# Schematic_v26.net
KiCad netlist of a schematic drawn in EAGLE
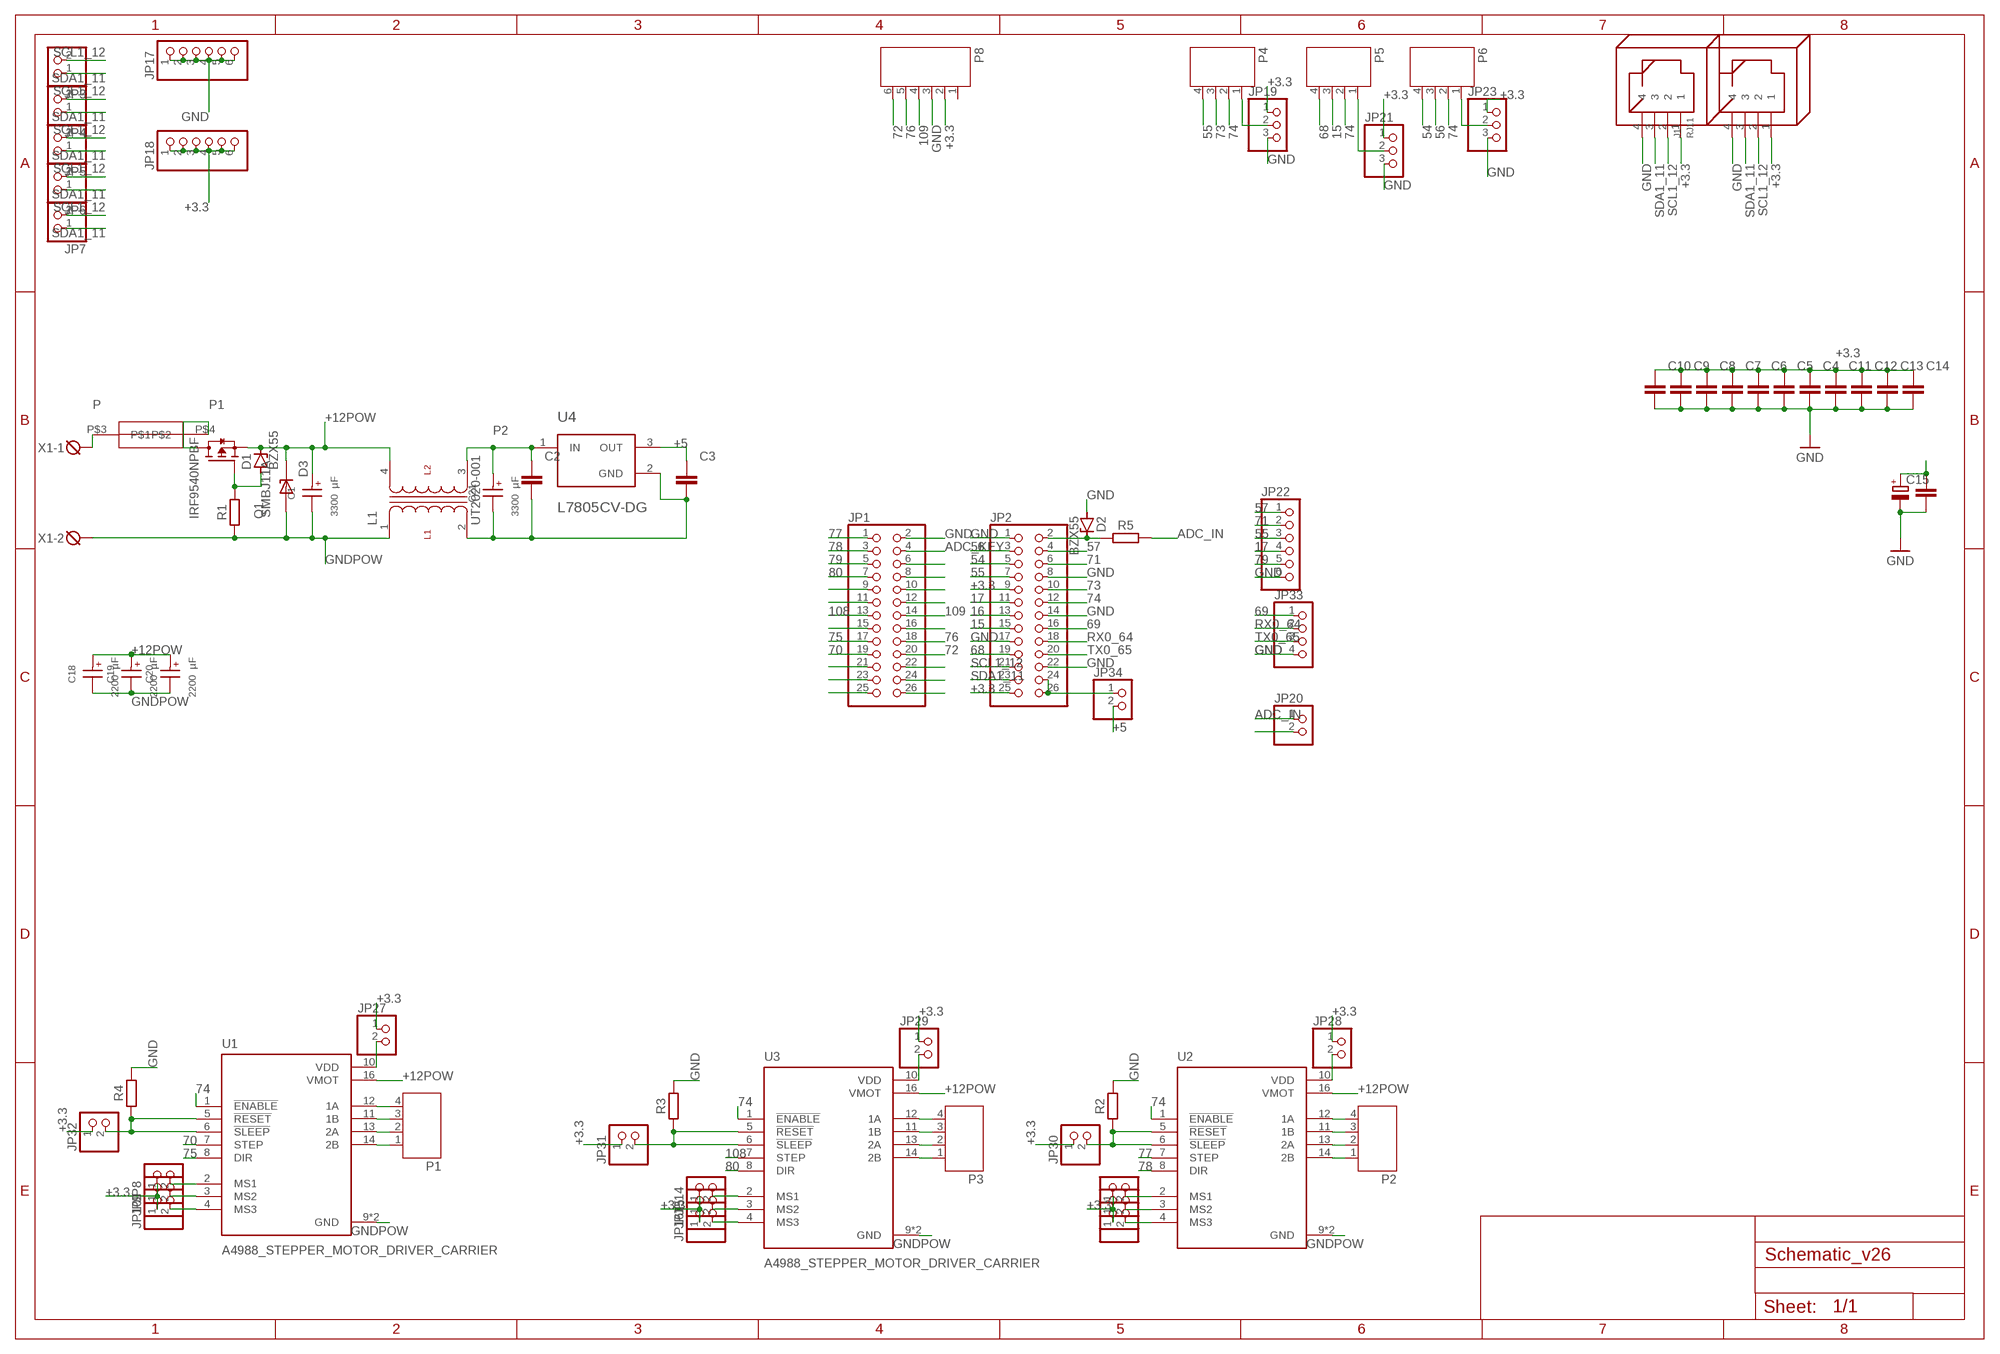
[diagram p0: schematic, sheet 1]

(export (version "E")
  (design (tool "Eeschema 10.0.6"))
  (components
    (comp (ref "C1")
      (value "3300 µF")
      (footprint "eagle-import:WCAP-AT1H_13X20(DXL)")
      (libsource (lib "eagle-import") (part "WCAP-AT1H_13X20_860240278009"))
    )
    (comp (ref "C2")
      (value "C_CHIP-1206(3216-METRIC)")
      (footprint "eagle-import:CAPC3216X135")
      (libsource (lib "eagle-import") (part "CCHIP-1206(3216-METRIC)_"))
    )
    (comp (ref "C3")
      (value "C_CHIP-0603(1608-METRIC)")
      (footprint "eagle-import:CAPC1608X85")
      (libsource (lib "eagle-import") (part "CCHIP-0603(1608-METRIC)_"))
    )
    (comp (ref "C4")
      (value "C_CHIP-0603(1608-METRIC)")
      (footprint "eagle-import:CAPC1608X85")
      (libsource (lib "eagle-import") (part "CCHIP-0603(1608-METRIC)_"))
    )
    (comp (ref "C5")
      (value "C_CHIP-0603(1608-METRIC)")
      (footprint "eagle-import:CAPC1608X85")
      (libsource (lib "eagle-import") (part "CCHIP-0603(1608-METRIC)_"))
    )
    (comp (ref "C6")
      (value "C_CHIP-0603(1608-METRIC)")
      (footprint "eagle-import:CAPC1608X85")
      (libsource (lib "eagle-import") (part "CCHIP-0603(1608-METRIC)_"))
    )
    (comp (ref "C7")
      (value "C_CHIP-0603(1608-METRIC)")
      (footprint "eagle-import:CAPC1608X85")
      (libsource (lib "eagle-import") (part "CCHIP-0603(1608-METRIC)_"))
    )
    (comp (ref "C8")
      (value "C_CHIP-0603(1608-METRIC)")
      (footprint "eagle-import:CAPC1608X85")
      (libsource (lib "eagle-import") (part "CCHIP-0603(1608-METRIC)_"))
    )
    (comp (ref "C9")
      (value "C_CHIP-0603(1608-METRIC)")
      (footprint "eagle-import:CAPC1608X85")
      (libsource (lib "eagle-import") (part "CCHIP-0603(1608-METRIC)_"))
    )
    (comp (ref "C10")
      (value "C_CHIP-0603(1608-METRIC)")
      (footprint "eagle-import:CAPC1608X85")
      (libsource (lib "eagle-import") (part "CCHIP-0603(1608-METRIC)_"))
    )
    (comp (ref "C11")
      (value "C_CHIP-1206(3216-METRIC)")
      (footprint "eagle-import:CAPC3216X135")
      (libsource (lib "eagle-import") (part "CCHIP-1206(3216-METRIC)_"))
    )
    (comp (ref "C12")
      (value "C_CHIP-1206(3216-METRIC)")
      (footprint "eagle-import:CAPC3216X135")
      (libsource (lib "eagle-import") (part "CCHIP-1206(3216-METRIC)_"))
    )
    (comp (ref "C13")
      (value "C_CHIP-1206(3216-METRIC)")
      (footprint "eagle-import:CAPC3216X135")
      (libsource (lib "eagle-import") (part "CCHIP-1206(3216-METRIC)_"))
    )
    (comp (ref "C14")
      (value "C_CHIP-1206(3216-METRIC)")
      (footprint "eagle-import:CAPC3216X135")
      (libsource (lib "eagle-import") (part "CCHIP-1206(3216-METRIC)_"))
    )
    (comp (ref "C15")
      (value "C-POL_RADIAL-11MM-DIA")
      (footprint "eagle-import:CAPPRD508W65D1000H1100B")
      (libsource (lib "eagle-import") (part "C-POLRADIAL-11MM-DIA_"))
    )
    (comp (ref "C18")
      (value "2200 µF")
      (footprint "eagle-import:WCAP-AT1H_13X20(DXL)")
      (libsource (lib "eagle-import") (part "WCAP-AT1H_13X20_860240278009"))
    )
    (comp (ref "C19")
      (value "2200 µF")
      (footprint "eagle-import:WCAP-AT1H_13X20(DXL)")
      (libsource (lib "eagle-import") (part "WCAP-AT1H_13X20_860240278009"))
    )
    (comp (ref "C20")
      (value "2200 µF")
      (footprint "eagle-import:WCAP-AT1H_13X20(DXL)")
      (libsource (lib "eagle-import") (part "WCAP-AT1H_13X20_860240278009"))
    )
    (comp (ref "C21")
      (value "3300 µF")
      (footprint "eagle-import:WCAP-AT1H_13X20(DXL)")
      (libsource (lib "eagle-import") (part "WCAP-AT1H_13X20_860240278009"))
    )
    (comp (ref "C22")
      (value "C_CHIP-1206(3216-METRIC)")
      (footprint "eagle-import:CAPC3216X135")
      (libsource (lib "eagle-import") (part "CCHIP-1206(3216-METRIC)_"))
    )
    (comp (ref "D1")
      (value "BZX55")
      (footprint "eagle-import:DO35Z10")
      (libsource (lib "eagle-import") (part "BZX55"))
    )
    (comp (ref "D2")
      (value "BZX55")
      (footprint "eagle-import:DO35Z10")
      (libsource (lib "eagle-import") (part "BZX55"))
    )
    (comp (ref "D3")
      (value "SMBJ11A")
      (footprint "eagle-import:DIOM4336X265N")
      (fields (field (name "MF") "Taiwan Semiconductor"))
      (libsource (lib "eagle-import") (part "SMBJ11A"))
    )
    (comp (ref "J1")
      (value "RJ11")
      (footprint "eagle-import:RJ11")
      (libsource (lib "eagle-import") (part "RJ11"))
    )
    (comp (ref "J3")
      (value "RJ11")
      (footprint "eagle-import:RJ11")
      (libsource (lib "eagle-import") (part "RJ11"))
    )
    (comp (ref "JP1")
      (value "PINHD-2X13")
      (footprint "eagle-import:2X13")
      (libsource (lib "eagle-import") (part "PINHD-2X13"))
    )
    (comp (ref "JP2")
      (value "PINHD-2X13")
      (footprint "eagle-import:2X13")
      (libsource (lib "eagle-import") (part "PINHD-2X13"))
    )
    (comp (ref "JP3")
      (value "PINHD-1X2")
      (footprint "eagle-import:1X02")
      (libsource (lib "eagle-import") (part "PINHD-1X2"))
    )
    (comp (ref "JP4")
      (value "PINHD-1X2")
      (footprint "eagle-import:1X02")
      (libsource (lib "eagle-import") (part "PINHD-1X2"))
    )
    (comp (ref "JP5")
      (value "PINHD-1X2")
      (footprint "eagle-import:1X02")
      (libsource (lib "eagle-import") (part "PINHD-1X2"))
    )
    (comp (ref "JP6")
      (value "PINHD-1X2")
      (footprint "eagle-import:1X02")
      (libsource (lib "eagle-import") (part "PINHD-1X2"))
    )
    (comp (ref "JP7")
      (value "PINHD-1X2")
      (footprint "eagle-import:1X02")
      (libsource (lib "eagle-import") (part "PINHD-1X2"))
    )
    (comp (ref "JP8")
      (value "PINHD-1X2")
      (footprint "eagle-import:1X02")
      (libsource (lib "eagle-import") (part "PINHD-1X2"))
    )
    (comp (ref "JP9")
      (value "PINHD-1X2")
      (footprint "eagle-import:1X02")
      (libsource (lib "eagle-import") (part "PINHD-1X2"))
    )
    (comp (ref "JP10")
      (value "PINHD-1X2")
      (footprint "eagle-import:1X02")
      (libsource (lib "eagle-import") (part "PINHD-1X2"))
    )
    (comp (ref "JP11")
      (value "PINHD-1X2")
      (footprint "eagle-import:1X02")
      (libsource (lib "eagle-import") (part "PINHD-1X2"))
    )
    (comp (ref "JP12")
      (value "PINHD-1X2")
      (footprint "eagle-import:1X02")
      (libsource (lib "eagle-import") (part "PINHD-1X2"))
    )
    (comp (ref "JP13")
      (value "PINHD-1X2")
      (footprint "eagle-import:1X02")
      (libsource (lib "eagle-import") (part "PINHD-1X2"))
    )
    (comp (ref "JP14")
      (value "PINHD-1X2")
      (footprint "eagle-import:1X02")
      (libsource (lib "eagle-import") (part "PINHD-1X2"))
    )
    (comp (ref "JP15")
      (value "PINHD-1X2")
      (footprint "eagle-import:1X02")
      (libsource (lib "eagle-import") (part "PINHD-1X2"))
    )
    (comp (ref "JP16")
      (value "PINHD-1X2")
      (footprint "eagle-import:1X02")
      (libsource (lib "eagle-import") (part "PINHD-1X2"))
    )
    (comp (ref "JP17")
      (value "PINHD-1X6")
      (footprint "eagle-import:1X06")
      (libsource (lib "eagle-import") (part "PINHD-1X6"))
    )
    (comp (ref "JP18")
      (value "PINHD-1X6")
      (footprint "eagle-import:1X06")
      (libsource (lib "eagle-import") (part "PINHD-1X6"))
    )
    (comp (ref "JP19")
      (value "PINHD-1X3")
      (footprint "eagle-import:1X03")
      (libsource (lib "eagle-import") (part "PINHD-1X3"))
    )
    (comp (ref "JP20")
      (value "PINHD-1X2")
      (footprint "eagle-import:1X02")
      (libsource (lib "eagle-import") (part "PINHD-1X2"))
    )
    (comp (ref "JP21")
      (value "PINHD-1X3")
      (footprint "eagle-import:1X03")
      (libsource (lib "eagle-import") (part "PINHD-1X3"))
    )
    (comp (ref "JP22")
      (value "PINHD-1X6")
      (footprint "eagle-import:1X06")
      (libsource (lib "eagle-import") (part "PINHD-1X6"))
    )
    (comp (ref "JP23")
      (value "PINHD-1X3")
      (footprint "eagle-import:1X03")
      (libsource (lib "eagle-import") (part "PINHD-1X3"))
    )
    (comp (ref "JP27")
      (value "PINHD-1X2")
      (footprint "eagle-import:1X02")
      (libsource (lib "eagle-import") (part "PINHD-1X2"))
    )
    (comp (ref "JP28")
      (value "PINHD-1X2")
      (footprint "eagle-import:1X02")
      (libsource (lib "eagle-import") (part "PINHD-1X2"))
    )
    (comp (ref "JP29")
      (value "PINHD-1X2")
      (footprint "eagle-import:1X02")
      (libsource (lib "eagle-import") (part "PINHD-1X2"))
    )
    (comp (ref "JP30")
      (value "PINHD-1X2")
      (footprint "eagle-import:1X02")
      (libsource (lib "eagle-import") (part "PINHD-1X2"))
    )
    (comp (ref "JP31")
      (value "PINHD-1X2")
      (footprint "eagle-import:1X02")
      (libsource (lib "eagle-import") (part "PINHD-1X2"))
    )
    (comp (ref "JP32")
      (value "PINHD-1X2")
      (footprint "eagle-import:1X02")
      (libsource (lib "eagle-import") (part "PINHD-1X2"))
    )
    (comp (ref "JP33")
      (value "PINHD-1X4")
      (footprint "eagle-import:1X04")
      (libsource (lib "eagle-import") (part "PINHD-1X4"))
    )
    (comp (ref "JP34")
      (value "PINHD-1X2")
      (footprint "eagle-import:1X02")
      (libsource (lib "eagle-import") (part "PINHD-1X2"))
    )
    (comp (ref "L1")
      (value "UT2020-001")
      (footprint "eagle-import:IND_UT2020-001")
      (fields (field (name "MF") "Triad Magnetics"))
      (libsource (lib "eagle-import") (part "UT2020-001"))
    )
    (comp (ref "P1")
      (value "JST-PH4")
      (footprint "eagle-import:JST-PH4")
      (libsource (lib "eagle-import") (part "JST-PH4"))
    )
    (comp (ref "P2")
      (value "JST-PH4")
      (footprint "eagle-import:JST-PH4")
      (libsource (lib "eagle-import") (part "JST-PH4"))
    )
    (comp (ref "P3")
      (value "JST-PH4")
      (footprint "eagle-import:JST-PH4")
      (libsource (lib "eagle-import") (part "JST-PH4"))
    )
    (comp (ref "P4")
      (value "JST-PH4")
      (footprint "eagle-import:JST-PH4")
      (libsource (lib "eagle-import") (part "JST-PH4"))
    )
    (comp (ref "P5")
      (value "JST-PH4")
      (footprint "eagle-import:JST-PH4")
      (libsource (lib "eagle-import") (part "JST-PH4"))
    )
    (comp (ref "P6")
      (value "JST-PH4")
      (footprint "eagle-import:JST-PH4")
      (libsource (lib "eagle-import") (part "JST-PH4"))
    )
    (comp (ref "P8")
      (value "JST-PH6")
      (footprint "eagle-import:JST-PH6")
      (libsource (lib "eagle-import") (part "JST-PH6"))
    )
    (comp (ref "Q1")
      (value "IRF9540NPBF")
      (footprint "eagle-import:TO254P1052X465X1989-3")
      (fields (field (name "MF") "Infineon Technologies"))
      (libsource (lib "eagle-import") (part "IRF9540NPBF"))
    )
    (comp (ref "R1")
      (value "R_AXIAL-7.2MM-PITCH")
      (footprint "eagle-import:RESAD724W46L381D178B")
      (libsource (lib "eagle-import") (part "RAXIAL-7.2MM-PITCH_"))
    )
    (comp (ref "R2")
      (value "R_CHIP-1206(3216-METRIC)")
      (footprint "eagle-import:RESC3216X70")
      (libsource (lib "eagle-import") (part "RCHIP-1206(3216-METRIC)_"))
    )
    (comp (ref "R3")
      (value "R_CHIP-1206(3216-METRIC)")
      (footprint "eagle-import:RESC3216X70")
      (libsource (lib "eagle-import") (part "RCHIP-1206(3216-METRIC)_"))
    )
    (comp (ref "R4")
      (value "R_CHIP-1206(3216-METRIC)")
      (footprint "eagle-import:RESC3216X70")
      (libsource (lib "eagle-import") (part "RCHIP-1206(3216-METRIC)_"))
    )
    (comp (ref "R5")
      (value "R_CHIP-1206(3216-METRIC)")
      (footprint "eagle-import:RESC3216X70")
      (libsource (lib "eagle-import") (part "RCHIP-1206(3216-METRIC)_"))
    )
    (comp (ref "U$1")
      (value "POJ")
      (footprint "eagle-import:POJ")
      (libsource (lib "eagle-import") (part "POJ"))
    )
    (comp (ref "U1")
      (value "A4988_STEPPER_MOTOR_DRIVER_CARRIER")
      (footprint "eagle-import:MODULE_A4988_STEPPER_MOTOR_DRIVER_CARRIER")
      (fields (field (name "MF") "Pololu") (field (name "MP") "A4988 STEPPER MOTOR DRIVER CARRIER"))
      (libsource (lib "eagle-import") (part "A4988_STEPPER_MOTOR_DRIVER_CARRIER"))
    )
    (comp (ref "U2")
      (value "A4988_STEPPER_MOTOR_DRIVER_CARRIER")
      (footprint "eagle-import:MODULE_A4988_STEPPER_MOTOR_DRIVER_CARRIER")
      (fields (field (name "MF") "Pololu") (field (name "MP") "A4988 STEPPER MOTOR DRIVER CARRIER"))
      (libsource (lib "eagle-import") (part "A4988_STEPPER_MOTOR_DRIVER_CARRIER"))
    )
    (comp (ref "U3")
      (value "A4988_STEPPER_MOTOR_DRIVER_CARRIER")
      (footprint "eagle-import:MODULE_A4988_STEPPER_MOTOR_DRIVER_CARRIER")
      (fields (field (name "MF") "Pololu") (field (name "MP") "A4988 STEPPER MOTOR DRIVER CARRIER"))
      (libsource (lib "eagle-import") (part "A4988_STEPPER_MOTOR_DRIVER_CARRIER"))
    )
    (comp (ref "U4")
      (value "L7805CV-DG")
      (footprint "eagle-import:TO255P1040X460X2890-3")
      (fields (field (name "MF") "STMicroelectronics"))
      (libsource (lib "eagle-import") (part "L7805CV-DG"))
    )
    (comp (ref "X1")
      (value "DG3XX-02-3.5")
      (footprint "eagle-import:DG350-3.5-02P")
      (libsource (lib "eagle-import") (part "DG3XX-02-3.5"))
    )
  )
  (nets
    (net (code "1") (name "/+3.3") (class "Default")
      (node (ref "C10") (pin "1") (pinfunction "1_1") (pintype "passive"))
      (node (ref "C11") (pin "1") (pinfunction "1_1") (pintype "passive"))
      (node (ref "C12") (pin "1") (pinfunction "1_1") (pintype "passive"))
      (node (ref "C13") (pin "1") (pinfunction "1_1") (pintype "passive"))
      (node (ref "C14") (pin "1") (pinfunction "1_1") (pintype "passive"))
      (node (ref "C4") (pin "1") (pinfunction "1_1") (pintype "passive"))
      (node (ref "C5") (pin "1") (pinfunction "1_1") (pintype "passive"))
      (node (ref "C6") (pin "1") (pinfunction "1_1") (pintype "passive"))
      (node (ref "C7") (pin "1") (pinfunction "1_1") (pintype "passive"))
      (node (ref "C8") (pin "1") (pinfunction "1_1") (pintype "passive"))
      (node (ref "C9") (pin "1") (pinfunction "1_1") (pintype "passive"))
      (node (ref "J1") (pin "1") (pinfunction "1_1") (pintype "bidirectional"))
      (node (ref "J3") (pin "1") (pinfunction "1_1") (pintype "bidirectional"))
      (node (ref "JP10") (pin "1") (pinfunction "1_1") (pintype "passive"))
      (node (ref "JP11") (pin "1") (pinfunction "1_1") (pintype "passive"))
      (node (ref "JP12") (pin "1") (pinfunction "1_1") (pintype "passive"))
      (node (ref "JP13") (pin "1") (pinfunction "1_1") (pintype "passive"))
      (node (ref "JP14") (pin "1") (pinfunction "1_1") (pintype "passive"))
      (node (ref "JP15") (pin "1") (pinfunction "1_1") (pintype "passive"))
      (node (ref "JP16") (pin "1") (pinfunction "1_1") (pintype "passive"))
      (node (ref "JP18") (pin "1") (pinfunction "1_1") (pintype "passive"))
      (node (ref "JP18") (pin "2") (pinfunction "2_2") (pintype "passive"))
      (node (ref "JP18") (pin "3") (pinfunction "3_3") (pintype "passive"))
      (node (ref "JP18") (pin "4") (pinfunction "4_4") (pintype "passive"))
      (node (ref "JP18") (pin "5") (pinfunction "5_5") (pintype "passive"))
      (node (ref "JP18") (pin "6") (pinfunction "6_6") (pintype "passive"))
      (node (ref "JP19") (pin "1") (pinfunction "1_1") (pintype "passive"))
      (node (ref "JP2") (pin "25") (pinfunction "25_25") (pintype "passive"))
      (node (ref "JP2") (pin "9") (pinfunction "9_9") (pintype "passive"))
      (node (ref "JP21") (pin "1") (pinfunction "1_1") (pintype "passive"))
      (node (ref "JP23") (pin "1") (pinfunction "1_1") (pintype "passive"))
      (node (ref "JP27") (pin "1") (pinfunction "1_1") (pintype "passive"))
      (node (ref "JP28") (pin "1") (pinfunction "1_1") (pintype "passive"))
      (node (ref "JP29") (pin "1") (pinfunction "1_1") (pintype "passive"))
      (node (ref "JP30") (pin "1") (pinfunction "1_1") (pintype "passive"))
      (node (ref "JP31") (pin "1") (pinfunction "1_1") (pintype "passive"))
      (node (ref "JP32") (pin "1") (pinfunction "1_1") (pintype "passive"))
      (node (ref "JP8") (pin "1") (pinfunction "1_1") (pintype "passive"))
      (node (ref "JP9") (pin "1") (pinfunction "1_1") (pintype "passive"))
      (node (ref "P8") (pin "2") (pinfunction "2_2") (pintype "passive"))
    )
    (net (code "2") (name "/+5") (class "Default")
      (node (ref "C15") (pin "1") (pinfunction "+_1") (pintype "passive"))
      (node (ref "C22") (pin "1") (pinfunction "1_1") (pintype "passive"))
      (node (ref "C3") (pin "1") (pinfunction "1_1") (pintype "passive"))
      (node (ref "JP34") (pin "2") (pinfunction "2_2") (pintype "passive"))
      (node (ref "U4") (pin "3") (pinfunction "OUT_3") (pintype "output"))
    )
    (net (code "3") (name "/+12POW") (class "Default")
      (node (ref "C1") (pin "1") (pinfunction "+_1") (pintype "passive"))
      (node (ref "C18") (pin "1") (pinfunction "+_1") (pintype "passive"))
      (node (ref "C19") (pin "1") (pinfunction "+_1") (pintype "passive"))
      (node (ref "C20") (pin "1") (pinfunction "+_1") (pintype "passive"))
      (node (ref "D1") (pin "C") (pinfunction "C_C") (pintype "passive"))
      (node (ref "D3") (pin "C") (pinfunction "C_C") (pintype "passive"))
      (node (ref "L1") (pin "4") (pinfunction "4_4") (pintype "passive"))
      (node (ref "Q1") (pin "3") (pinfunction "S_3") (pintype "passive"))
      (node (ref "U1") (pin "16") (pinfunction "VMOT_16") (pintype "power_in"))
      (node (ref "U2") (pin "16") (pinfunction "VMOT_16") (pintype "power_in"))
      (node (ref "U3") (pin "16") (pinfunction "VMOT_16") (pintype "power_in"))
    )
    (net (code "4") (name "/15") (class "Default")
      (node (ref "JP2") (pin "15") (pinfunction "15_15") (pintype "passive"))
      (node (ref "P5") (pin "3") (pinfunction "3_3") (pintype "passive"))
    )
    (net (code "5") (name "/16") (class "Default")
      (node (ref "JP2") (pin "13") (pinfunction "13_13") (pintype "passive"))
    )
    (net (code "6") (name "/17") (class "Default")
      (node (ref "JP2") (pin "11") (pinfunction "11_11") (pintype "passive"))
      (node (ref "JP22") (pin "4") (pinfunction "4_4") (pintype "passive"))
    )
    (net (code "7") (name "/54") (class "Default")
      (node (ref "JP2") (pin "5") (pinfunction "5_5") (pintype "passive"))
      (node (ref "P6") (pin "4") (pinfunction "4_4") (pintype "passive"))
    )
    (net (code "8") (name "/55") (class "Default")
      (node (ref "JP2") (pin "7") (pinfunction "7_7") (pintype "passive"))
      (node (ref "JP22") (pin "3") (pinfunction "3_3") (pintype "passive"))
      (node (ref "P4") (pin "4") (pinfunction "4_4") (pintype "passive"))
    )
    (net (code "9") (name "/56") (class "Default")
      (node (ref "JP2") (pin "3") (pinfunction "3_3") (pintype "passive"))
      (node (ref "P6") (pin "3") (pinfunction "3_3") (pintype "passive"))
    )
    (net (code "10") (name "/57") (class "Default")
      (node (ref "JP2") (pin "4") (pinfunction "4_4") (pintype "passive"))
      (node (ref "JP22") (pin "1") (pinfunction "1_1") (pintype "passive"))
    )
    (net (code "11") (name "/68") (class "Default")
      (node (ref "JP2") (pin "19") (pinfunction "19_19") (pintype "passive"))
      (node (ref "P5") (pin "4") (pinfunction "4_4") (pintype "passive"))
    )
    (net (code "12") (name "/69") (class "Default")
      (node (ref "JP2") (pin "16") (pinfunction "16_16") (pintype "passive"))
      (node (ref "JP33") (pin "1") (pinfunction "1_1") (pintype "passive"))
    )
    (net (code "13") (name "/70") (class "Default")
      (node (ref "JP1") (pin "19") (pinfunction "19_19") (pintype "passive"))
      (node (ref "U1") (pin "7") (pinfunction "STEP_7") (pintype "input"))
    )
    (net (code "14") (name "/71") (class "Default")
      (node (ref "JP2") (pin "6") (pinfunction "6_6") (pintype "passive"))
      (node (ref "JP22") (pin "2") (pinfunction "2_2") (pintype "passive"))
    )
    (net (code "15") (name "/72") (class "Default")
      (node (ref "JP1") (pin "20") (pinfunction "20_20") (pintype "passive"))
      (node (ref "P8") (pin "6") (pinfunction "6_6") (pintype "passive"))
    )
    (net (code "16") (name "/73") (class "Default")
      (node (ref "JP2") (pin "10") (pinfunction "10_10") (pintype "passive"))
      (node (ref "P4") (pin "3") (pinfunction "3_3") (pintype "passive"))
    )
    (net (code "17") (name "/74") (class "Default")
      (node (ref "JP2") (pin "12") (pinfunction "12_12") (pintype "passive"))
      (node (ref "P4") (pin "2") (pinfunction "2_2") (pintype "passive"))
      (node (ref "P5") (pin "2") (pinfunction "2_2") (pintype "passive"))
      (node (ref "P6") (pin "2") (pinfunction "2_2") (pintype "passive"))
      (node (ref "U1") (pin "1") (pinfunction "~{ENABLE}_1") (pintype "input"))
      (node (ref "U2") (pin "1") (pinfunction "~{ENABLE}_1") (pintype "input"))
      (node (ref "U3") (pin "1") (pinfunction "~{ENABLE}_1") (pintype "input"))
    )
    (net (code "18") (name "/75") (class "Default")
      (node (ref "JP1") (pin "17") (pinfunction "17_17") (pintype "passive"))
      (node (ref "U1") (pin "8") (pinfunction "DIR_8") (pintype "input"))
    )
    (net (code "19") (name "/76") (class "Default")
      (node (ref "JP1") (pin "18") (pinfunction "18_18") (pintype "passive"))
      (node (ref "P8") (pin "5") (pinfunction "5_5") (pintype "passive"))
    )
    (net (code "20") (name "/77") (class "Default")
      (node (ref "JP1") (pin "1") (pinfunction "1_1") (pintype "passive"))
      (node (ref "U2") (pin "7") (pinfunction "STEP_7") (pintype "input"))
    )
    (net (code "21") (name "/78") (class "Default")
      (node (ref "JP1") (pin "3") (pinfunction "3_3") (pintype "passive"))
      (node (ref "U2") (pin "8") (pinfunction "DIR_8") (pintype "input"))
    )
    (net (code "22") (name "/79") (class "Default")
      (node (ref "JP1") (pin "5") (pinfunction "5_5") (pintype "passive"))
      (node (ref "JP22") (pin "5") (pinfunction "5_5") (pintype "passive"))
    )
    (net (code "23") (name "/80") (class "Default")
      (node (ref "JP1") (pin "7") (pinfunction "7_7") (pintype "passive"))
      (node (ref "U3") (pin "8") (pinfunction "DIR_8") (pintype "input"))
    )
    (net (code "24") (name "/108") (class "Default")
      (node (ref "JP1") (pin "13") (pinfunction "13_13") (pintype "passive"))
      (node (ref "U3") (pin "7") (pinfunction "STEP_7") (pintype "input"))
    )
    (net (code "25") (name "/109") (class "Default")
      (node (ref "JP1") (pin "14") (pinfunction "14_14") (pintype "passive"))
      (node (ref "P8") (pin "4") (pinfunction "4_4") (pintype "passive"))
    )
    (net (code "26") (name "/ADC_IN") (class "Default")
      (node (ref "JP20") (pin "1") (pinfunction "1_1") (pintype "passive"))
      (node (ref "R5") (pin "2") (pinfunction "2_2") (pintype "passive"))
    )
    (net (code "27") (name "/ADC_KEY") (class "Default")
      (node (ref "JP1") (pin "4") (pinfunction "4_4") (pintype "passive"))
    )
    (net (code "28") (name "/GNDPOW") (class "Default")
      (node (ref "C1") (pin "2") (pinfunction "-_2") (pintype "passive"))
      (node (ref "C18") (pin "2") (pinfunction "-_2") (pintype "passive"))
      (node (ref "C19") (pin "2") (pinfunction "-_2") (pintype "passive"))
      (node (ref "C20") (pin "2") (pinfunction "-_2") (pintype "passive"))
      (node (ref "D3") (pin "A") (pinfunction "A_A") (pintype "passive"))
      (node (ref "L1") (pin "1") (pinfunction "1_1") (pintype "passive"))
      (node (ref "R1") (pin "1") (pinfunction "1_1") (pintype "passive"))
      (node (ref "U1") (pin "15") (pinfunction "GND_15") (pintype "power_in"))
      (node (ref "U1") (pin "9") (pinfunction "GND_9") (pintype "power_in"))
      (node (ref "U2") (pin "15") (pinfunction "GND_15") (pintype "power_in"))
      (node (ref "U2") (pin "9") (pinfunction "GND_9") (pintype "power_in"))
      (node (ref "U3") (pin "15") (pinfunction "GND_15") (pintype "power_in"))
      (node (ref "U3") (pin "9") (pinfunction "GND_9") (pintype "power_in"))
      (node (ref "X1") (pin "2") (pinfunction "KL_2") (pintype "passive"))
    )
    (net (code "29") (name "/P") (class "Default")
      (node (ref "U$1") (pin "P$3") (pinfunction "P$1_P$3") (pintype "bidirectional"))
      (node (ref "X1") (pin "1") (pinfunction "KL_1") (pintype "passive"))
    )
    (net (code "30") (name "/P1") (class "Default")
      (node (ref "Q1") (pin "2") (pinfunction "D_2") (pintype "passive"))
      (node (ref "U$1") (pin "P$4") (pinfunction "P$2_P$4") (pintype "bidirectional"))
    )
    (net (code "31") (name "/P2") (class "Default")
      (node (ref "C2") (pin "1") (pinfunction "1_1") (pintype "passive"))
      (node (ref "C21") (pin "1") (pinfunction "+_1") (pintype "passive"))
      (node (ref "L1") (pin "3") (pinfunction "3_3") (pintype "passive"))
      (node (ref "U4") (pin "1") (pinfunction "IN_1") (pintype "input"))
    )
    (net (code "32") (name "/RX0_64") (class "Default")
      (node (ref "JP2") (pin "18") (pinfunction "18_18") (pintype "passive"))
      (node (ref "JP33") (pin "2") (pinfunction "2_2") (pintype "passive"))
    )
    (net (code "33") (name "/SCL1_12") (class "Default")
      (node (ref "J1") (pin "2") (pinfunction "2_2") (pintype "bidirectional"))
      (node (ref "J3") (pin "2") (pinfunction "2_2") (pintype "bidirectional"))
      (node (ref "JP2") (pin "21") (pinfunction "21_21") (pintype "passive"))
      (node (ref "JP3") (pin "2") (pinfunction "2_2") (pintype "passive"))
      (node (ref "JP4") (pin "2") (pinfunction "2_2") (pintype "passive"))
      (node (ref "JP5") (pin "2") (pinfunction "2_2") (pintype "passive"))
      (node (ref "JP6") (pin "2") (pinfunction "2_2") (pintype "passive"))
      (node (ref "JP7") (pin "2") (pinfunction "2_2") (pintype "passive"))
    )
    (net (code "34") (name "/SDA1_11") (class "Default")
      (node (ref "J1") (pin "3") (pinfunction "3_3") (pintype "bidirectional"))
      (node (ref "J3") (pin "3") (pinfunction "3_3") (pintype "bidirectional"))
      (node (ref "JP2") (pin "23") (pinfunction "23_23") (pintype "passive"))
      (node (ref "JP3") (pin "1") (pinfunction "1_1") (pintype "passive"))
      (node (ref "JP4") (pin "1") (pinfunction "1_1") (pintype "passive"))
      (node (ref "JP5") (pin "1") (pinfunction "1_1") (pintype "passive"))
      (node (ref "JP6") (pin "1") (pinfunction "1_1") (pintype "passive"))
      (node (ref "JP7") (pin "1") (pinfunction "1_1") (pintype "passive"))
    )
    (net (code "35") (name "/TX0_65") (class "Default")
      (node (ref "JP2") (pin "20") (pinfunction "20_20") (pintype "passive"))
      (node (ref "JP33") (pin "3") (pinfunction "3_3") (pintype "passive"))
    )
    (net (code "36") (name "GND") (class "Default")
      (node (ref "C10") (pin "2") (pinfunction "2_2") (pintype "passive"))
      (node (ref "C11") (pin "2") (pinfunction "2_2") (pintype "passive"))
      (node (ref "C12") (pin "2") (pinfunction "2_2") (pintype "passive"))
      (node (ref "C13") (pin "2") (pinfunction "2_2") (pintype "passive"))
      (node (ref "C14") (pin "2") (pinfunction "2_2") (pintype "passive"))
      (node (ref "C15") (pin "2") (pinfunction "-_2") (pintype "passive"))
      (node (ref "C2") (pin "2") (pinfunction "2_2") (pintype "passive"))
      (node (ref "C21") (pin "2") (pinfunction "-_2") (pintype "passive"))
      (node (ref "C22") (pin "2") (pinfunction "2_2") (pintype "passive"))
      (node (ref "C3") (pin "2") (pinfunction "2_2") (pintype "passive"))
      (node (ref "C4") (pin "2") (pinfunction "2_2") (pintype "passive"))
      (node (ref "C5") (pin "2") (pinfunction "2_2") (pintype "passive"))
      (node (ref "C6") (pin "2") (pinfunction "2_2") (pintype "passive"))
      (node (ref "C7") (pin "2") (pinfunction "2_2") (pintype "passive"))
      (node (ref "C8") (pin "2") (pinfunction "2_2") (pintype "passive"))
      (node (ref "C9") (pin "2") (pinfunction "2_2") (pintype "passive"))
      (node (ref "D2") (pin "A") (pinfunction "A_A") (pintype "passive"))
      (node (ref "J1") (pin "4") (pinfunction "4_4") (pintype "bidirectional"))
      (node (ref "J3") (pin "4") (pinfunction "4_4") (pintype "bidirectional"))
      (node (ref "JP1") (pin "2") (pinfunction "2_2") (pintype "passive"))
      (node (ref "JP17") (pin "1") (pinfunction "1_1") (pintype "passive"))
      (node (ref "JP17") (pin "2") (pinfunction "2_2") (pintype "passive"))
      (node (ref "JP17") (pin "3") (pinfunction "3_3") (pintype "passive"))
      (node (ref "JP17") (pin "4") (pinfunction "4_4") (pintype "passive"))
      (node (ref "JP17") (pin "5") (pinfunction "5_5") (pintype "passive"))
      (node (ref "JP17") (pin "6") (pinfunction "6_6") (pintype "passive"))
      (node (ref "JP19") (pin "3") (pinfunction "3_3") (pintype "passive"))
      (node (ref "JP2") (pin "1") (pinfunction "1_1") (pintype "passive"))
      (node (ref "JP2") (pin "14") (pinfunction "14_14") (pintype "passive"))
      (node (ref "JP2") (pin "17") (pinfunction "17_17") (pintype "passive"))
      (node (ref "JP2") (pin "22") (pinfunction "22_22") (pintype "passive"))
      (node (ref "JP2") (pin "8") (pinfunction "8_8") (pintype "passive"))
      (node (ref "JP20") (pin "2") (pinfunction "2_2") (pintype "passive"))
      (node (ref "JP21") (pin "3") (pinfunction "3_3") (pintype "passive"))
      (node (ref "JP22") (pin "6") (pinfunction "6_6") (pintype "passive"))
      (node (ref "JP23") (pin "3") (pinfunction "3_3") (pintype "passive"))
      (node (ref "JP33") (pin "4") (pinfunction "4_4") (pintype "passive"))
      (node (ref "L1") (pin "2") (pinfunction "2_2") (pintype "passive"))
      (node (ref "P8") (pin "3") (pinfunction "3_3") (pintype "passive"))
      (node (ref "R2") (pin "2") (pinfunction "2_2") (pintype "passive"))
      (node (ref "R3") (pin "2") (pinfunction "2_2") (pintype "passive"))
      (node (ref "R4") (pin "2") (pinfunction "2_2") (pintype "passive"))
      (node (ref "U4") (pin "2") (pinfunction "GND_2") (pintype "power_in"))
    )
    (net (code "37") (name "Net-(D2-PadC)") (class "Default")
      (node (ref "D2") (pin "C") (pinfunction "C_C") (pintype "passive"))
      (node (ref "JP2") (pin "2") (pinfunction "2_2") (pintype "passive"))
      (node (ref "R5") (pin "1") (pinfunction "1_1") (pintype "passive"))
    )
    (net (code "38") (name "Net-(JP2-Pad24)") (class "Default")
      (node (ref "JP2") (pin "24") (pinfunction "24_24") (pintype "passive"))
      (node (ref "JP2") (pin "26") (pinfunction "26_26") (pintype "passive"))
      (node (ref "JP34") (pin "1") (pinfunction "1_1") (pintype "passive"))
    )
    (net (code "39") (name "Net-(JP19-Pad2)") (class "Default")
      (node (ref "JP19") (pin "2") (pinfunction "2_2") (pintype "passive"))
      (node (ref "P4") (pin "1") (pinfunction "1_1") (pintype "passive"))
    )
    (net (code "40") (name "Net-(JP21-Pad2)") (class "Default")
      (node (ref "JP21") (pin "2") (pinfunction "2_2") (pintype "passive"))
      (node (ref "P5") (pin "1") (pinfunction "1_1") (pintype "passive"))
    )
    (net (code "41") (name "Net-(JP23-Pad2)") (class "Default")
      (node (ref "JP23") (pin "2") (pinfunction "2_2") (pintype "passive"))
      (node (ref "P6") (pin "1") (pinfunction "1_1") (pintype "passive"))
    )
    (net (code "42") (name "Net-(Q1-G)") (class "Default")
      (node (ref "D1") (pin "A") (pinfunction "A_A") (pintype "passive"))
      (node (ref "Q1") (pin "1") (pinfunction "G_1") (pintype "passive"))
      (node (ref "R1") (pin "2") (pinfunction "2_2") (pintype "passive"))
    )
    (net (code "43") (name "Net-(U1-1A)") (class "Default")
      (node (ref "P1") (pin "4") (pinfunction "4_4") (pintype "passive"))
      (node (ref "U1") (pin "12") (pinfunction "1A_12") (pintype "output"))
    )
    (net (code "44") (name "Net-(U1-1B)") (class "Default")
      (node (ref "P1") (pin "3") (pinfunction "3_3") (pintype "passive"))
      (node (ref "U1") (pin "11") (pinfunction "1B_11") (pintype "output"))
    )
    (net (code "45") (name "Net-(U1-2A)") (class "Default")
      (node (ref "P1") (pin "2") (pinfunction "2_2") (pintype "passive"))
      (node (ref "U1") (pin "13") (pinfunction "2A_13") (pintype "output"))
    )
    (net (code "46") (name "Net-(U1-2B)") (class "Default")
      (node (ref "P1") (pin "1") (pinfunction "1_1") (pintype "passive"))
      (node (ref "U1") (pin "14") (pinfunction "2B_14") (pintype "output"))
    )
    (net (code "47") (name "Net-(U1-MS1)") (class "Default")
      (node (ref "JP8") (pin "2") (pinfunction "2_2") (pintype "passive"))
      (node (ref "U1") (pin "2") (pinfunction "MS1_2") (pintype "input"))
    )
    (net (code "48") (name "Net-(U1-MS2)") (class "Default")
      (node (ref "JP9") (pin "2") (pinfunction "2_2") (pintype "passive"))
      (node (ref "U1") (pin "3") (pinfunction "MS2_3") (pintype "input"))
    )
    (net (code "49") (name "Net-(U1-MS3)") (class "Default")
      (node (ref "JP10") (pin "2") (pinfunction "2_2") (pintype "passive"))
      (node (ref "U1") (pin "4") (pinfunction "MS3_4") (pintype "input"))
    )
    (net (code "50") (name "Net-(U1-VDD)") (class "Default")
      (node (ref "JP27") (pin "2") (pinfunction "2_2") (pintype "passive"))
      (node (ref "U1") (pin "10") (pinfunction "VDD_10") (pintype "power_in"))
    )
    (net (code "51") (name "Net-(U1-~{RESET})") (class "Default")
      (node (ref "JP32") (pin "2") (pinfunction "2_2") (pintype "passive"))
      (node (ref "R4") (pin "1") (pinfunction "1_1") (pintype "passive"))
      (node (ref "U1") (pin "5") (pinfunction "~{RESET}_5") (pintype "input"))
      (node (ref "U1") (pin "6") (pinfunction "~{SLEEP}_6") (pintype "input"))
    )
    (net (code "52") (name "Net-(U2-1A)") (class "Default")
      (node (ref "P2") (pin "4") (pinfunction "4_4") (pintype "passive"))
      (node (ref "U2") (pin "12") (pinfunction "1A_12") (pintype "output"))
    )
    (net (code "53") (name "Net-(U2-1B)") (class "Default")
      (node (ref "P2") (pin "3") (pinfunction "3_3") (pintype "passive"))
      (node (ref "U2") (pin "11") (pinfunction "1B_11") (pintype "output"))
    )
    (net (code "54") (name "Net-(U2-2A)") (class "Default")
      (node (ref "P2") (pin "2") (pinfunction "2_2") (pintype "passive"))
      (node (ref "U2") (pin "13") (pinfunction "2A_13") (pintype "output"))
    )
    (net (code "55") (name "Net-(U2-2B)") (class "Default")
      (node (ref "P2") (pin "1") (pinfunction "1_1") (pintype "passive"))
      (node (ref "U2") (pin "14") (pinfunction "2B_14") (pintype "output"))
    )
    (net (code "56") (name "Net-(U2-MS1)") (class "Default")
      (node (ref "JP11") (pin "2") (pinfunction "2_2") (pintype "passive"))
      (node (ref "U2") (pin "2") (pinfunction "MS1_2") (pintype "input"))
    )
    (net (code "57") (name "Net-(U2-MS2)") (class "Default")
      (node (ref "JP12") (pin "2") (pinfunction "2_2") (pintype "passive"))
      (node (ref "U2") (pin "3") (pinfunction "MS2_3") (pintype "input"))
    )
    (net (code "58") (name "Net-(U2-MS3)") (class "Default")
      (node (ref "JP13") (pin "2") (pinfunction "2_2") (pintype "passive"))
      (node (ref "U2") (pin "4") (pinfunction "MS3_4") (pintype "input"))
    )
    (net (code "59") (name "Net-(U2-VDD)") (class "Default")
      (node (ref "JP28") (pin "2") (pinfunction "2_2") (pintype "passive"))
      (node (ref "U2") (pin "10") (pinfunction "VDD_10") (pintype "power_in"))
    )
    (net (code "60") (name "Net-(U2-~{RESET})") (class "Default")
      (node (ref "JP30") (pin "2") (pinfunction "2_2") (pintype "passive"))
      (node (ref "R2") (pin "1") (pinfunction "1_1") (pintype "passive"))
      (node (ref "U2") (pin "5") (pinfunction "~{RESET}_5") (pintype "input"))
      (node (ref "U2") (pin "6") (pinfunction "~{SLEEP}_6") (pintype "input"))
    )
    (net (code "61") (name "Net-(U3-1A)") (class "Default")
      (node (ref "P3") (pin "4") (pinfunction "4_4") (pintype "passive"))
      (node (ref "U3") (pin "12") (pinfunction "1A_12") (pintype "output"))
    )
    (net (code "62") (name "Net-(U3-1B)") (class "Default")
      (node (ref "P3") (pin "3") (pinfunction "3_3") (pintype "passive"))
      (node (ref "U3") (pin "11") (pinfunction "1B_11") (pintype "output"))
    )
    (net (code "63") (name "Net-(U3-2A)") (class "Default")
      (node (ref "P3") (pin "2") (pinfunction "2_2") (pintype "passive"))
      (node (ref "U3") (pin "13") (pinfunction "2A_13") (pintype "output"))
    )
    (net (code "64") (name "Net-(U3-2B)") (class "Default")
      (node (ref "P3") (pin "1") (pinfunction "1_1") (pintype "passive"))
      (node (ref "U3") (pin "14") (pinfunction "2B_14") (pintype "output"))
    )
    (net (code "65") (name "Net-(U3-MS1)") (class "Default")
      (node (ref "JP14") (pin "2") (pinfunction "2_2") (pintype "passive"))
      (node (ref "U3") (pin "2") (pinfunction "MS1_2") (pintype "input"))
    )
    (net (code "66") (name "Net-(U3-MS2)") (class "Default")
      (node (ref "JP15") (pin "2") (pinfunction "2_2") (pintype "passive"))
      (node (ref "U3") (pin "3") (pinfunction "MS2_3") (pintype "input"))
    )
    (net (code "67") (name "Net-(U3-MS3)") (class "Default")
      (node (ref "JP16") (pin "2") (pinfunction "2_2") (pintype "passive"))
      (node (ref "U3") (pin "4") (pinfunction "MS3_4") (pintype "input"))
    )
    (net (code "68") (name "Net-(U3-VDD)") (class "Default")
      (node (ref "JP29") (pin "2") (pinfunction "2_2") (pintype "passive"))
      (node (ref "U3") (pin "10") (pinfunction "VDD_10") (pintype "power_in"))
    )
    (net (code "69") (name "Net-(U3-~{RESET})") (class "Default")
      (node (ref "JP31") (pin "2") (pinfunction "2_2") (pintype "passive"))
      (node (ref "R3") (pin "1") (pinfunction "1_1") (pintype "passive"))
      (node (ref "U3") (pin "5") (pinfunction "~{RESET}_5") (pintype "input"))
      (node (ref "U3") (pin "6") (pinfunction "~{SLEEP}_6") (pintype "input"))
    )
    (net (code "70") (name "unconnected-(JP1-Pad6)") (class "Default")
      (node (ref "JP1") (pin "6") (pinfunction "6_6") (pintype "passive"))
    )
    (net (code "71") (name "unconnected-(JP1-Pad8)") (class "Default")
      (node (ref "JP1") (pin "8") (pinfunction "8_8") (pintype "passive"))
    )
    (net (code "72") (name "unconnected-(JP1-Pad9)") (class "Default")
      (node (ref "JP1") (pin "9") (pinfunction "9_9") (pintype "passive"))
    )
    (net (code "73") (name "unconnected-(JP1-Pad10)") (class "Default")
      (node (ref "JP1") (pin "10") (pinfunction "10_10") (pintype "passive"))
    )
    (net (code "74") (name "unconnected-(JP1-Pad11)") (class "Default")
      (node (ref "JP1") (pin "11") (pinfunction "11_11") (pintype "passive"))
    )
    (net (code "75") (name "unconnected-(JP1-Pad12)") (class "Default")
      (node (ref "JP1") (pin "12") (pinfunction "12_12") (pintype "passive"))
    )
    (net (code "76") (name "unconnected-(JP1-Pad15)") (class "Default")
      (node (ref "JP1") (pin "15") (pinfunction "15_15") (pintype "passive"))
    )
    (net (code "77") (name "unconnected-(JP1-Pad16)") (class "Default")
      (node (ref "JP1") (pin "16") (pinfunction "16_16") (pintype "passive"))
    )
    (net (code "78") (name "unconnected-(JP1-Pad21)") (class "Default")
      (node (ref "JP1") (pin "21") (pinfunction "21_21") (pintype "passive"))
    )
    (net (code "79") (name "unconnected-(JP1-Pad22)") (class "Default")
      (node (ref "JP1") (pin "22") (pinfunction "22_22") (pintype "passive"))
    )
    (net (code "80") (name "unconnected-(JP1-Pad23)") (class "Default")
      (node (ref "JP1") (pin "23") (pinfunction "23_23") (pintype "passive"))
    )
    (net (code "81") (name "unconnected-(JP1-Pad24)") (class "Default")
      (node (ref "JP1") (pin "24") (pinfunction "24_24") (pintype "passive"))
    )
    (net (code "82") (name "unconnected-(JP1-Pad25)") (class "Default")
      (node (ref "JP1") (pin "25") (pinfunction "25_25") (pintype "passive"))
    )
    (net (code "83") (name "unconnected-(JP1-Pad26)") (class "Default")
      (node (ref "JP1") (pin "26") (pinfunction "26_26") (pintype "passive"))
    )
    (net (code "84") (name "unconnected-(P8-Pad1)") (class "Default")
      (node (ref "P8") (pin "1") (pinfunction "1_1") (pintype "passive"))
    )
  )
)
